# bt_bio.net
KiCad netlist of a schematic drawn in EAGLE
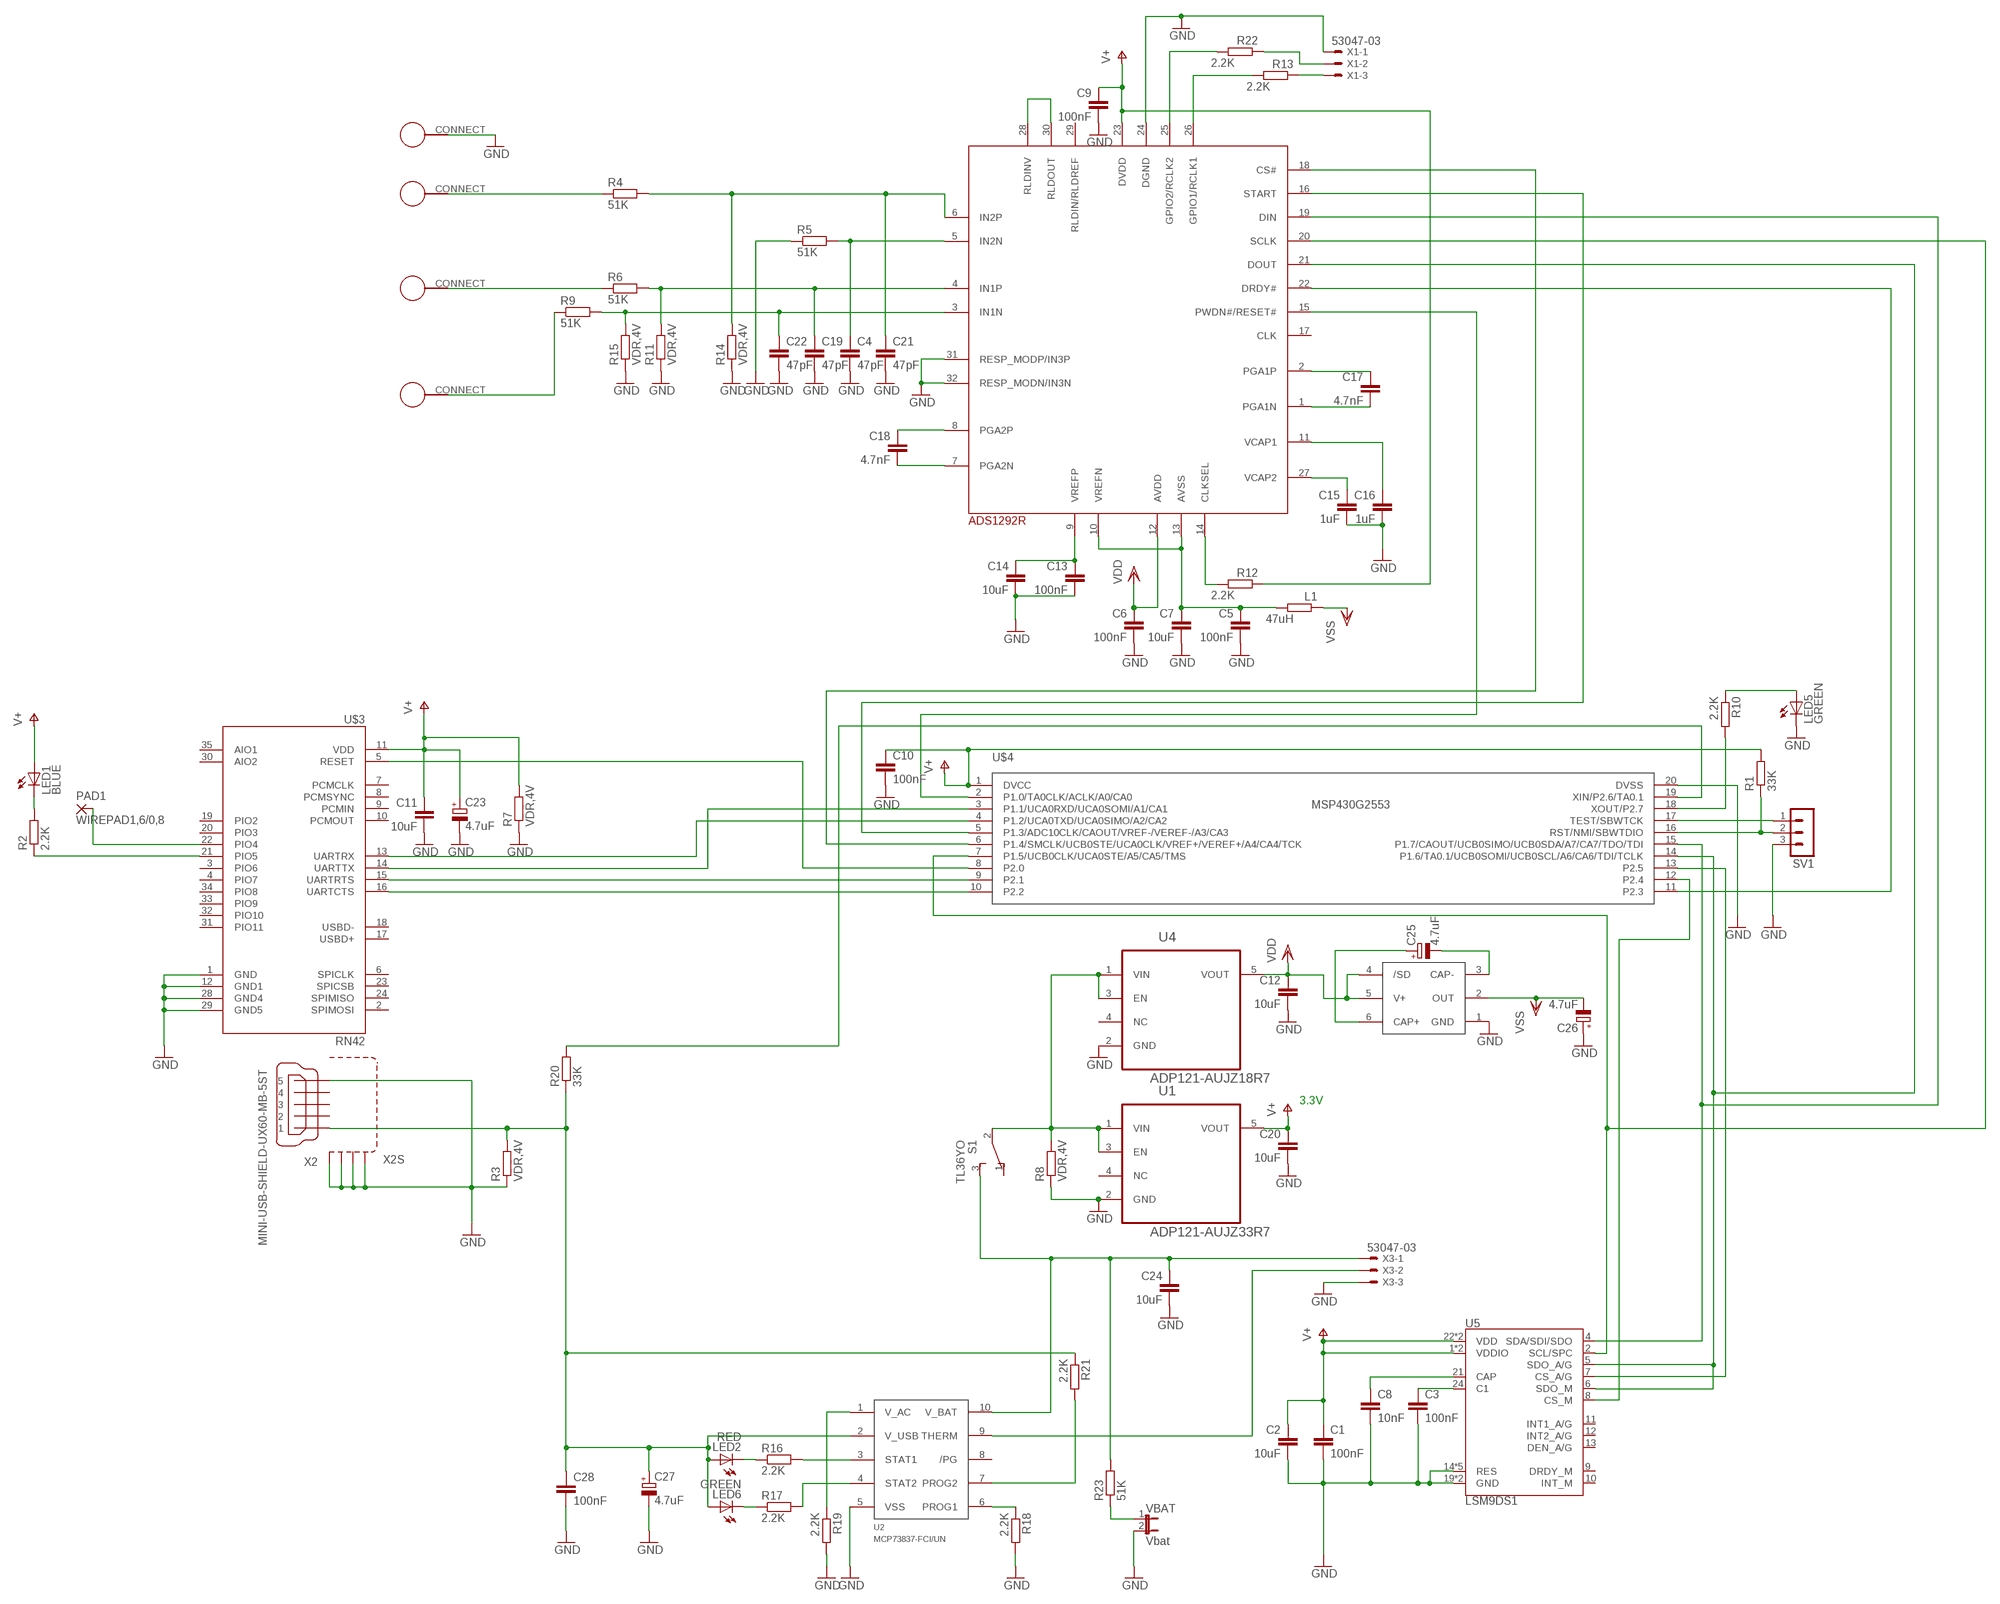
[diagram p0: schematic, sheet 1]

(export (version "E")
  (design (tool "Eeschema 10.0.6"))
  (components
    (comp (ref "ADS1292R")
      (value "ADS1292R")
      (footprint "eagle-import:TQFP-32")
      (libsource (lib "eagle-import") (part "ADS1292R"))
    )
    (comp (ref "C1")
      (value "100nF")
      (footprint "eagle-import:C0603")
      (libsource (lib "eagle-import") (part "C-EUC0603"))
    )
    (comp (ref "C2")
      (value "10uF")
      (footprint "eagle-import:C1206")
      (libsource (lib "eagle-import") (part "C-EUC1206"))
    )
    (comp (ref "C3")
      (value "100nF")
      (footprint "eagle-import:C0603")
      (libsource (lib "eagle-import") (part "C-EUC0603"))
    )
    (comp (ref "C4")
      (value "47pF")
      (footprint "eagle-import:C0603")
      (libsource (lib "eagle-import") (part "C-EUC0603"))
    )
    (comp (ref "C5")
      (value "100nF")
      (footprint "eagle-import:C0603")
      (libsource (lib "eagle-import") (part "C-EUC0603"))
    )
    (comp (ref "C6")
      (value "100nF")
      (footprint "eagle-import:C0603")
      (libsource (lib "eagle-import") (part "C-EUC0603"))
    )
    (comp (ref "C7")
      (value "10uF")
      (footprint "eagle-import:C1206")
      (libsource (lib "eagle-import") (part "C-EUC1206"))
    )
    (comp (ref "C8")
      (value "10nF")
      (footprint "eagle-import:C0603")
      (libsource (lib "eagle-import") (part "C-EUC0603"))
    )
    (comp (ref "C9")
      (value "100nF")
      (footprint "eagle-import:C0603")
      (libsource (lib "eagle-import") (part "C-EUC0603"))
    )
    (comp (ref "C10")
      (value "100nF")
      (footprint "eagle-import:C0603")
      (libsource (lib "eagle-import") (part "C-EUC0603"))
    )
    (comp (ref "C11")
      (value "10uF")
      (footprint "eagle-import:C1206")
      (libsource (lib "eagle-import") (part "C-EUC1206"))
    )
    (comp (ref "C12")
      (value "10uF")
      (footprint "eagle-import:C1206")
      (libsource (lib "eagle-import") (part "C-EUC1206"))
    )
    (comp (ref "C13")
      (value "100nF")
      (footprint "eagle-import:C0603")
      (libsource (lib "eagle-import") (part "C-EUC0603"))
    )
    (comp (ref "C14")
      (value "10uF")
      (footprint "eagle-import:C1206")
      (libsource (lib "eagle-import") (part "C-EUC1206"))
    )
    (comp (ref "C15")
      (value "1uF")
      (footprint "eagle-import:C0603")
      (libsource (lib "eagle-import") (part "C-EUC0603"))
    )
    (comp (ref "C16")
      (value "1uF")
      (footprint "eagle-import:C0603")
      (libsource (lib "eagle-import") (part "C-EUC0603"))
    )
    (comp (ref "C17")
      (value "4.7nF")
      (footprint "eagle-import:C0603")
      (libsource (lib "eagle-import") (part "C-EUC0603"))
    )
    (comp (ref "C18")
      (value "4.7nF")
      (footprint "eagle-import:C0603")
      (libsource (lib "eagle-import") (part "C-EUC0603"))
    )
    (comp (ref "C19")
      (value "47pF")
      (footprint "eagle-import:C0603")
      (libsource (lib "eagle-import") (part "C-EUC0603"))
    )
    (comp (ref "C20")
      (value "10uF")
      (footprint "eagle-import:C1206")
      (libsource (lib "eagle-import") (part "C-EUC1206"))
    )
    (comp (ref "C21")
      (value "47pF")
      (footprint "eagle-import:C0603")
      (libsource (lib "eagle-import") (part "C-EUC0603"))
    )
    (comp (ref "C22")
      (value "47pF")
      (footprint "eagle-import:C0603")
      (libsource (lib "eagle-import") (part "C-EUC0603"))
    )
    (comp (ref "C23")
      (value "4.7uF")
      (footprint "eagle-import:SMC_C")
      (libsource (lib "eagle-import") (part "CPOL-EUSMCC"))
    )
    (comp (ref "C24")
      (value "10uF")
      (footprint "eagle-import:C1206")
      (libsource (lib "eagle-import") (part "C-EUC1206"))
    )
    (comp (ref "C25")
      (value "4.7uF")
      (footprint "eagle-import:SMC_C")
      (libsource (lib "eagle-import") (part "CPOL-EUSMCC"))
    )
    (comp (ref "C26")
      (value "4.7uF")
      (footprint "eagle-import:SMC_C")
      (libsource (lib "eagle-import") (part "CPOL-EUSMCC"))
    )
    (comp (ref "C27")
      (value "4.7uF")
      (footprint "eagle-import:SMC_C")
      (libsource (lib "eagle-import") (part "CPOL-EUSMCC"))
    )
    (comp (ref "C28")
      (value "100nF")
      (footprint "eagle-import:C0603")
      (libsource (lib "eagle-import") (part "C-EUC0603"))
    )
    (comp (ref "L1")
      (value "47uH")
      (footprint "eagle-import:R0805")
      (libsource (lib "eagle-import") (part "R-EU_R0805"))
    )
    (comp (ref "LED1")
      (value "BLUE")
      (footprint "eagle-import:CHIPLED_0805")
      (libsource (lib "eagle-import") (part "LEDCHIPLED_0805"))
    )
    (comp (ref "LED2")
      (value "RED")
      (footprint "eagle-import:CHIPLED_0805")
      (libsource (lib "eagle-import") (part "LEDCHIPLED_0805"))
    )
    (comp (ref "LED5")
      (value "GREEN")
      (footprint "eagle-import:CHIPLED_0805")
      (libsource (lib "eagle-import") (part "LEDCHIPLED_0805"))
    )
    (comp (ref "LED6")
      (value "GREEN")
      (footprint "eagle-import:CHIPLED_0805")
      (libsource (lib "eagle-import") (part "LEDCHIPLED_0805"))
    )
    (comp (ref "PAD1")
      (value "WIREPAD1,6/0,8")
      (footprint "eagle-import:1,6_0,8")
      (libsource (lib "eagle-import") (part "WIREPAD1,6/0,8"))
    )
    (comp (ref "R1")
      (value "33K")
      (footprint "eagle-import:R0603")
      (libsource (lib "eagle-import") (part "resistor_R-EU_R0603"))
    )
    (comp (ref "R2")
      (value "2.2K")
      (footprint "eagle-import:R0603")
      (libsource (lib "eagle-import") (part "R-EU_R0603"))
    )
    (comp (ref "R3")
      (value "VDR,4V")
      (footprint "eagle-import:R0805")
      (libsource (lib "eagle-import") (part "R-EU_R0805"))
    )
    (comp (ref "R4")
      (value "51K")
      (footprint "eagle-import:R0603")
      (libsource (lib "eagle-import") (part "R-EU_R0603"))
    )
    (comp (ref "R5")
      (value "51K")
      (footprint "eagle-import:R0603")
      (libsource (lib "eagle-import") (part "R-EU_R0603"))
    )
    (comp (ref "R6")
      (value "51K")
      (footprint "eagle-import:R0603")
      (libsource (lib "eagle-import") (part "R-EU_R0603"))
    )
    (comp (ref "R7")
      (value "VDR,4V")
      (footprint "eagle-import:R0805")
      (libsource (lib "eagle-import") (part "R-EU_R0805"))
    )
    (comp (ref "R8")
      (value "VDR,4V")
      (footprint "eagle-import:R0805")
      (libsource (lib "eagle-import") (part "R-EU_R0805"))
    )
    (comp (ref "R9")
      (value "51K")
      (footprint "eagle-import:R0603")
      (libsource (lib "eagle-import") (part "R-EU_R0603"))
    )
    (comp (ref "R10")
      (value "2.2K")
      (footprint "eagle-import:R0603")
      (libsource (lib "eagle-import") (part "R-EU_R0603"))
    )
    (comp (ref "R11")
      (value "VDR,4V")
      (footprint "eagle-import:R0805")
      (libsource (lib "eagle-import") (part "R-EU_R0805"))
    )
    (comp (ref "R12")
      (value "2.2K")
      (footprint "eagle-import:R0603")
      (libsource (lib "eagle-import") (part "R-EU_R0603"))
    )
    (comp (ref "R13")
      (value "2.2K")
      (footprint "eagle-import:R0603")
      (libsource (lib "eagle-import") (part "R-EU_R0603"))
    )
    (comp (ref "R14")
      (value "VDR,4V")
      (footprint "eagle-import:R0805")
      (libsource (lib "eagle-import") (part "R-EU_R0805"))
    )
    (comp (ref "R15")
      (value "VDR,4V")
      (footprint "eagle-import:R0805")
      (libsource (lib "eagle-import") (part "R-EU_R0805"))
    )
    (comp (ref "R16")
      (value "2.2K")
      (footprint "eagle-import:R0603")
      (libsource (lib "eagle-import") (part "R-EU_R0603"))
    )
    (comp (ref "R17")
      (value "2.2K")
      (footprint "eagle-import:R0603")
      (libsource (lib "eagle-import") (part "R-EU_R0603"))
    )
    (comp (ref "R18")
      (value "2.2K")
      (footprint "eagle-import:R0603")
      (libsource (lib "eagle-import") (part "R-EU_R0603"))
    )
    (comp (ref "R19")
      (value "2.2K")
      (footprint "eagle-import:R0603")
      (libsource (lib "eagle-import") (part "R-EU_R0603"))
    )
    (comp (ref "R20")
      (value "33K")
      (footprint "eagle-import:R0603")
      (libsource (lib "eagle-import") (part "resistor_R-EU_R0603"))
    )
    (comp (ref "R21")
      (value "2.2K")
      (footprint "eagle-import:R0603")
      (libsource (lib "eagle-import") (part "R-EU_R0603"))
    )
    (comp (ref "R22")
      (value "2.2K")
      (footprint "eagle-import:R0603")
      (libsource (lib "eagle-import") (part "R-EU_R0603"))
    )
    (comp (ref "R23")
      (value "51K")
      (footprint "eagle-import:R0603")
      (libsource (lib "eagle-import") (part "R-EU_R0603"))
    )
    (comp (ref "S1")
      (value "TL36YO")
      (footprint "eagle-import:TL3XYO")
      (libsource (lib "eagle-import") (part "TL36YO"))
    )
    (comp (ref "SV1")
      (value "MA03-1")
      (footprint "eagle-import:MA03-1")
      (libsource (lib "eagle-import") (part "MA03-1"))
    )
    (comp (ref "U$3")
      (value "RN42")
      (footprint "eagle-import:SPARKFUN_RN41")
      (libsource (lib "eagle-import") (part "SPARKFUN_BLUETOOTH-RN41{dblquote}"))
    )
    (comp (ref "U$4")
      (value "MSP430G2553")
      (footprint "eagle-import:TSSOP20")
      (libsource (lib "eagle-import") (part "MSP430G2553"))
    )
    (comp (ref "U$5")
      (value "4MMCONNECT")
      (footprint "eagle-import:4MMCONNECT")
      (libsource (lib "eagle-import") (part "4MMCONNECT"))
    )
    (comp (ref "U$7")
      (value "4MMCONNECT")
      (footprint "eagle-import:4MMCONNECT")
      (libsource (lib "eagle-import") (part "4MMCONNECT"))
    )
    (comp (ref "U$9")
      (value "4MMCONNECT")
      (footprint "eagle-import:4MMCONNECT")
      (libsource (lib "eagle-import") (part "4MMCONNECT"))
    )
    (comp (ref "U$10")
      (value "4MMCONNECT")
      (footprint "eagle-import:4MMCONNECT")
      (libsource (lib "eagle-import") (part "4MMCONNECT"))
    )
    (comp (ref "U$12")
      (value "LM2664")
      (footprint "eagle-import:SOT-23-5")
      (libsource (lib "eagle-import") (part "LM2664"))
    )
    (comp (ref "U1")
      (value "ADP121-AUJZ33R7")
      (footprint "eagle-import:SOT95P280X100-5N")
      (libsource (lib "eagle-import") (part "ADP121-AUJZ33R7"))
    )
    (comp (ref "U2")
      (value "MCP73837-FCI/UN")
      (footprint "eagle-import:MSOP10")
      (libsource (lib "eagle-import") (part "MCP73837"))
    )
    (comp (ref "U4")
      (value "ADP121-AUJZ18R7")
      (footprint "eagle-import:SOT95P280X100-5N")
      (fields (field (name "MPN") "ADP121-AUJZ33R7"))
      (libsource (lib "eagle-import") (part "ADP121-AUJZ33R7"))
    )
    (comp (ref "U5")
      (value "LSM9DS1")
      (footprint "eagle-import:LGA24-8X4")
      (libsource (lib "eagle-import") (part "LSM9DS1"))
    )
    (comp (ref "VBAT")
      (value "Vbat")
      (footprint "eagle-import:JP1")
      (libsource (lib "eagle-import") (part "JP1E"))
    )
    (comp (ref "X1")
      (value "53047-03")
      (footprint "eagle-import:53047-03")
      (fields (field (name "MPN") "530470310"))
      (libsource (lib "eagle-import") (part "53?-03047"))
    )
    (comp (ref "X2")
      (value "MINI-USB-SHIELD-UX60-MB-5ST")
      (footprint "eagle-import:UX60-MB-5ST")
      (libsource (lib "eagle-import") (part "MINI-USB-SHIELD-UX60-MB-5ST"))
    )
    (comp (ref "X3")
      (value "53047-03")
      (footprint "eagle-import:53047-03")
      (fields (field (name "MPN") "530470310"))
      (libsource (lib "eagle-import") (part "53?-03047"))
    )
  )
  (nets
    (net (code "1") (name "GND") (class "Default")
      (node (ref "ADS1292R") (pin "24") (pinfunction "DGND_24") (pintype "bidirectional"))
      (node (ref "ADS1292R") (pin "31") (pinfunction "RESP_MODP/IN3P_31") (pintype "bidirectional"))
      (node (ref "ADS1292R") (pin "32") (pinfunction "RESP_MODN/IN3N_32") (pintype "bidirectional"))
      (node (ref "C1") (pin "2") (pinfunction "2_2") (pintype "passive"))
      (node (ref "C10") (pin "2") (pinfunction "2_2") (pintype "passive"))
      (node (ref "C11") (pin "2") (pinfunction "2_2") (pintype "passive"))
      (node (ref "C12") (pin "2") (pinfunction "2_2") (pintype "passive"))
      (node (ref "C13") (pin "2") (pinfunction "2_2") (pintype "passive"))
      (node (ref "C14") (pin "2") (pinfunction "2_2") (pintype "passive"))
      (node (ref "C15") (pin "2") (pinfunction "2_2") (pintype "passive"))
      (node (ref "C16") (pin "2") (pinfunction "2_2") (pintype "passive"))
      (node (ref "C19") (pin "2") (pinfunction "2_2") (pintype "passive"))
      (node (ref "C2") (pin "2") (pinfunction "2_2") (pintype "passive"))
      (node (ref "C20") (pin "2") (pinfunction "2_2") (pintype "passive"))
      (node (ref "C21") (pin "2") (pinfunction "2_2") (pintype "passive"))
      (node (ref "C22") (pin "2") (pinfunction "2_2") (pintype "passive"))
      (node (ref "C23") (pin "-") (pinfunction "-_-") (pintype "passive"))
      (node (ref "C24") (pin "2") (pinfunction "2_2") (pintype "passive"))
      (node (ref "C26") (pin "+") (pinfunction "+_+") (pintype "passive"))
      (node (ref "C27") (pin "-") (pinfunction "-_-") (pintype "passive"))
      (node (ref "C28") (pin "2") (pinfunction "2_2") (pintype "passive"))
      (node (ref "C3") (pin "2") (pinfunction "2_2") (pintype "passive"))
      (node (ref "C4") (pin "2") (pinfunction "2_2") (pintype "passive"))
      (node (ref "C5") (pin "2") (pinfunction "2_2") (pintype "passive"))
      (node (ref "C6") (pin "2") (pinfunction "2_2") (pintype "passive"))
      (node (ref "C7") (pin "2") (pinfunction "2_2") (pintype "passive"))
      (node (ref "C8") (pin "2") (pinfunction "2_2") (pintype "passive"))
      (node (ref "C9") (pin "2") (pinfunction "2_2") (pintype "passive"))
      (node (ref "LED5") (pin "C") (pinfunction "C_C") (pintype "passive"))
      (node (ref "R11") (pin "1") (pinfunction "1_1") (pintype "passive"))
      (node (ref "R14") (pin "1") (pinfunction "1_1") (pintype "passive"))
      (node (ref "R15") (pin "1") (pinfunction "1_1") (pintype "passive"))
      (node (ref "R18") (pin "2") (pinfunction "2_2") (pintype "passive"))
      (node (ref "R19") (pin "2") (pinfunction "2_2") (pintype "passive"))
      (node (ref "R3") (pin "1") (pinfunction "1_1") (pintype "passive"))
      (node (ref "R5") (pin "1") (pinfunction "1_1") (pintype "passive"))
      (node (ref "R7") (pin "1") (pinfunction "1_1") (pintype "passive"))
      (node (ref "R8") (pin "1") (pinfunction "1_1") (pintype "passive"))
      (node (ref "SV1") (pin "3") (pinfunction "3_3") (pintype "passive"))
      (node (ref "U$12") (pin "1") (pinfunction "GND_1") (pintype "power_in"))
      (node (ref "U$3") (pin "1") (pinfunction "GND_1") (pintype "bidirectional"))
      (node (ref "U$3") (pin "12") (pinfunction "GND1_12") (pintype "bidirectional"))
      (node (ref "U$3") (pin "28") (pinfunction "GND4_28") (pintype "bidirectional"))
      (node (ref "U$3") (pin "29") (pinfunction "GND5_29") (pintype "bidirectional"))
      (node (ref "U$4") (pin "20") (pinfunction "DVSS_20") (pintype "bidirectional"))
      (node (ref "U$5") (pin "CONNECT") (pinfunction "CONNECT_CONNECT") (pintype "passive"))
      (node (ref "U1") (pin "2") (pinfunction "GND_2") (pintype "passive"))
      (node (ref "U2") (pin "5") (pinfunction "VSS_5") (pintype "bidirectional"))
      (node (ref "U4") (pin "2") (pinfunction "GND_2") (pintype "passive"))
      (node (ref "U5") (pin "14") (pinfunction "RES_14") (pintype "bidirectional"))
      (node (ref "U5") (pin "15") (pinfunction "RES_15") (pintype "bidirectional"))
      (node (ref "U5") (pin "16") (pinfunction "RES_16") (pintype "bidirectional"))
      (node (ref "U5") (pin "17") (pinfunction "RES_17") (pintype "bidirectional"))
      (node (ref "U5") (pin "18") (pinfunction "RES_18") (pintype "bidirectional"))
      (node (ref "U5") (pin "19") (pinfunction "GND_19") (pintype "bidirectional"))
      (node (ref "U5") (pin "20") (pinfunction "GND_20") (pintype "bidirectional"))
      (node (ref "VBAT") (pin "2") (pinfunction "2_2") (pintype "passive"))
      (node (ref "X1") (pin "1") (pinfunction "S_1") (pintype "passive"))
      (node (ref "X2") (pin "5") (pinfunction "5_5") (pintype "input"))
      (node (ref "X2") (pin "M1") (pinfunction "S1_M1") (pintype "passive"))
      (node (ref "X2") (pin "M2") (pinfunction "S2_M2") (pintype "passive"))
      (node (ref "X2") (pin "M3") (pinfunction "S3_M3") (pintype "passive"))
      (node (ref "X2") (pin "M4") (pinfunction "S4_M4") (pintype "passive"))
      (node (ref "X3") (pin "3") (pinfunction "S_3") (pintype "passive"))
    )
    (net (code "2") (name "Net-(ADS1292R-AVSS)") (class "Default")
      (node (ref "ADS1292R") (pin "10") (pinfunction "VREFN_10") (pintype "bidirectional"))
      (node (ref "ADS1292R") (pin "13") (pinfunction "AVSS_13") (pintype "bidirectional"))
      (node (ref "C5") (pin "1") (pinfunction "1_1") (pintype "passive"))
      (node (ref "C7") (pin "1") (pinfunction "1_1") (pintype "passive"))
      (node (ref "L1") (pin "2") (pinfunction "2_2") (pintype "passive"))
    )
    (net (code "3") (name "Net-(ADS1292R-CLKSEL)") (class "Default")
      (node (ref "ADS1292R") (pin "14") (pinfunction "CLKSEL_14") (pintype "bidirectional"))
      (node (ref "R12") (pin "2") (pinfunction "2_2") (pintype "passive"))
    )
    (net (code "4") (name "Net-(ADS1292R-CS#)") (class "Default")
      (node (ref "ADS1292R") (pin "18") (pinfunction "CS#_18") (pintype "bidirectional"))
      (node (ref "U$4") (pin "6") (pinfunction "P1.4/SMCLK/UCB0STE/UCA0CLK/VREF+/VEREF+/A4/CA4/TCK_6") (pintype "bidirectional"))
    )
    (net (code "5") (name "Net-(ADS1292R-DIN)") (class "Default")
      (node (ref "ADS1292R") (pin "19") (pinfunction "DIN_19") (pintype "bidirectional"))
      (node (ref "U$4") (pin "15") (pinfunction "P1.7/CAOUT/UCB0SIMO/UCB0SDA/A7/CA7/TDO/TDI_15") (pintype "bidirectional"))
      (node (ref "U5") (pin "4") (pinfunction "SDA/SDI/SDO_4") (pintype "bidirectional"))
    )
    (net (code "6") (name "Net-(ADS1292R-DOUT)") (class "Default")
      (node (ref "ADS1292R") (pin "21") (pinfunction "DOUT_21") (pintype "bidirectional"))
      (node (ref "U$4") (pin "14") (pinfunction "P1.6/TA0.1/UCB0SOMI/UCB0SCL/A6/CA6/TDI/TCLK_14") (pintype "bidirectional"))
      (node (ref "U5") (pin "5") (pinfunction "SDO_A/G_5") (pintype "bidirectional"))
      (node (ref "U5") (pin "6") (pinfunction "SDO_M_6") (pintype "bidirectional"))
    )
    (net (code "7") (name "Net-(ADS1292R-DRDY#)") (class "Default")
      (node (ref "ADS1292R") (pin "22") (pinfunction "DRDY#_22") (pintype "bidirectional"))
      (node (ref "U$4") (pin "11") (pinfunction "P2.3_11") (pintype "bidirectional"))
    )
    (net (code "8") (name "Net-(ADS1292R-GPIO1{slash}RCLK1)") (class "Default")
      (node (ref "ADS1292R") (pin "26") (pinfunction "GPIO1/RCLK1_26") (pintype "bidirectional"))
      (node (ref "R13") (pin "2") (pinfunction "2_2") (pintype "passive"))
    )
    (net (code "9") (name "Net-(ADS1292R-GPIO2{slash}RCLK2)") (class "Default")
      (node (ref "ADS1292R") (pin "25") (pinfunction "GPIO2/RCLK2_25") (pintype "bidirectional"))
      (node (ref "R22") (pin "2") (pinfunction "2_2") (pintype "passive"))
    )
    (net (code "10") (name "Net-(ADS1292R-IN1N)") (class "Default")
      (node (ref "ADS1292R") (pin "3") (pinfunction "IN1N_3") (pintype "bidirectional"))
      (node (ref "C22") (pin "1") (pinfunction "1_1") (pintype "passive"))
      (node (ref "R15") (pin "2") (pinfunction "2_2") (pintype "passive"))
      (node (ref "R9") (pin "2") (pinfunction "2_2") (pintype "passive"))
    )
    (net (code "11") (name "Net-(ADS1292R-IN1P)") (class "Default")
      (node (ref "ADS1292R") (pin "4") (pinfunction "IN1P_4") (pintype "bidirectional"))
      (node (ref "C19") (pin "1") (pinfunction "1_1") (pintype "passive"))
      (node (ref "R11") (pin "2") (pinfunction "2_2") (pintype "passive"))
      (node (ref "R6") (pin "2") (pinfunction "2_2") (pintype "passive"))
    )
    (net (code "12") (name "Net-(ADS1292R-IN2N)") (class "Default")
      (node (ref "ADS1292R") (pin "5") (pinfunction "IN2N_5") (pintype "bidirectional"))
      (node (ref "C4") (pin "1") (pinfunction "1_1") (pintype "passive"))
      (node (ref "R5") (pin "2") (pinfunction "2_2") (pintype "passive"))
    )
    (net (code "13") (name "Net-(ADS1292R-IN2P)") (class "Default")
      (node (ref "ADS1292R") (pin "6") (pinfunction "IN2P_6") (pintype "bidirectional"))
      (node (ref "C21") (pin "1") (pinfunction "1_1") (pintype "passive"))
      (node (ref "R14") (pin "2") (pinfunction "2_2") (pintype "passive"))
      (node (ref "R4") (pin "2") (pinfunction "2_2") (pintype "passive"))
    )
    (net (code "14") (name "Net-(ADS1292R-PGA1N)") (class "Default")
      (node (ref "ADS1292R") (pin "1") (pinfunction "PGA1N_1") (pintype "bidirectional"))
      (node (ref "C17") (pin "2") (pinfunction "2_2") (pintype "passive"))
    )
    (net (code "15") (name "Net-(ADS1292R-PGA1P)") (class "Default")
      (node (ref "ADS1292R") (pin "2") (pinfunction "PGA1P_2") (pintype "bidirectional"))
      (node (ref "C17") (pin "1") (pinfunction "1_1") (pintype "passive"))
    )
    (net (code "16") (name "Net-(ADS1292R-PGA2N)") (class "Default")
      (node (ref "ADS1292R") (pin "7") (pinfunction "PGA2N_7") (pintype "bidirectional"))
      (node (ref "C18") (pin "2") (pinfunction "2_2") (pintype "passive"))
    )
    (net (code "17") (name "Net-(ADS1292R-PGA2P)") (class "Default")
      (node (ref "ADS1292R") (pin "8") (pinfunction "PGA2P_8") (pintype "bidirectional"))
      (node (ref "C18") (pin "1") (pinfunction "1_1") (pintype "passive"))
    )
    (net (code "18") (name "Net-(ADS1292R-PWDN#{slash}RESET#)") (class "Default")
      (node (ref "ADS1292R") (pin "15") (pinfunction "PWDN#/RESET#_15") (pintype "bidirectional"))
      (node (ref "U$4") (pin "2") (pinfunction "P1.0/TA0CLK/ACLK/A0/CA0_2") (pintype "bidirectional"))
    )
    (net (code "19") (name "Net-(ADS1292R-RLDINV)") (class "Default")
      (node (ref "ADS1292R") (pin "28") (pinfunction "RLDINV_28") (pintype "bidirectional"))
      (node (ref "ADS1292R") (pin "30") (pinfunction "RLDOUT_30") (pintype "bidirectional"))
    )
    (net (code "20") (name "Net-(ADS1292R-SCLK)") (class "Default")
      (node (ref "ADS1292R") (pin "20") (pinfunction "SCLK_20") (pintype "bidirectional"))
      (node (ref "U$4") (pin "7") (pinfunction "P1.5/UCB0CLK/UCA0STE/A5/CA5/TMS_7") (pintype "bidirectional"))
      (node (ref "U5") (pin "2") (pinfunction "SCL/SPC_2") (pintype "bidirectional"))
    )
    (net (code "21") (name "Net-(ADS1292R-START)") (class "Default")
      (node (ref "ADS1292R") (pin "16") (pinfunction "START_16") (pintype "bidirectional"))
      (node (ref "U$4") (pin "5") (pinfunction "P1.3/ADC10CLK/CAOUT/VREF-/VEREF-/A3/CA3_5") (pintype "bidirectional"))
    )
    (net (code "22") (name "Net-(ADS1292R-VCAP1)") (class "Default")
      (node (ref "ADS1292R") (pin "11") (pinfunction "VCAP1_11") (pintype "bidirectional"))
      (node (ref "C16") (pin "1") (pinfunction "1_1") (pintype "passive"))
    )
    (net (code "23") (name "Net-(ADS1292R-VCAP2)") (class "Default")
      (node (ref "ADS1292R") (pin "27") (pinfunction "VCAP2_27") (pintype "bidirectional"))
      (node (ref "C15") (pin "1") (pinfunction "1_1") (pintype "passive"))
    )
    (net (code "24") (name "Net-(ADS1292R-VREFP)") (class "Default")
      (node (ref "ADS1292R") (pin "9") (pinfunction "VREFP_9") (pintype "bidirectional"))
      (node (ref "C13") (pin "1") (pinfunction "1_1") (pintype "passive"))
      (node (ref "C14") (pin "1") (pinfunction "1_1") (pintype "passive"))
    )
    (net (code "25") (name "Net-(LED1-PadC)") (class "Default")
      (node (ref "LED1") (pin "C") (pinfunction "C_C") (pintype "passive"))
      (node (ref "R2") (pin "2") (pinfunction "2_2") (pintype "passive"))
    )
    (net (code "26") (name "Net-(LED2-PadC)") (class "Default")
      (node (ref "LED2") (pin "C") (pinfunction "C_C") (pintype "passive"))
      (node (ref "R16") (pin "1") (pinfunction "1_1") (pintype "passive"))
    )
    (net (code "27") (name "Net-(LED5-PadA)") (class "Default")
      (node (ref "LED5") (pin "A") (pinfunction "A_A") (pintype "passive"))
      (node (ref "R10") (pin "1") (pinfunction "1_1") (pintype "passive"))
    )
    (net (code "28") (name "Net-(LED6-PadC)") (class "Default")
      (node (ref "LED6") (pin "C") (pinfunction "C_C") (pintype "passive"))
      (node (ref "R17") (pin "1") (pinfunction "1_1") (pintype "passive"))
    )
    (net (code "29") (name "Net-(PAD1-P)") (class "Default")
      (node (ref "PAD1") (pin "1") (pinfunction "P_1") (pintype "passive"))
      (node (ref "U$3") (pin "22") (pinfunction "PIO4_22") (pintype "bidirectional"))
    )
    (net (code "30") (name "Net-(R4-Pad1)") (class "Default")
      (node (ref "R4") (pin "1") (pinfunction "1_1") (pintype "passive"))
      (node (ref "U$7") (pin "CONNECT") (pinfunction "CONNECT_CONNECT") (pintype "passive"))
    )
    (net (code "31") (name "Net-(R6-Pad1)") (class "Default")
      (node (ref "R6") (pin "1") (pinfunction "1_1") (pintype "passive"))
      (node (ref "U$9") (pin "CONNECT") (pinfunction "CONNECT_CONNECT") (pintype "passive"))
    )
    (net (code "32") (name "Net-(R9-Pad1)") (class "Default")
      (node (ref "R9") (pin "1") (pinfunction "1_1") (pintype "passive"))
      (node (ref "U$10") (pin "CONNECT") (pinfunction "CONNECT_CONNECT") (pintype "passive"))
    )
    (net (code "33") (name "Net-(R23-Pad1)") (class "Default")
      (node (ref "R23") (pin "1") (pinfunction "1_1") (pintype "passive"))
      (node (ref "VBAT") (pin "1") (pinfunction "1_1") (pintype "passive"))
    )
    (net (code "34") (name "Net-(S1-P)") (class "Default")
      (node (ref "R8") (pin "2") (pinfunction "2_2") (pintype "passive"))
      (node (ref "S1") (pin "2") (pinfunction "P_2") (pintype "passive"))
      (node (ref "U1") (pin "1") (pinfunction "VIN_1") (pintype "input"))
      (node (ref "U1") (pin "3") (pinfunction "EN_3") (pintype "input"))
      (node (ref "U4") (pin "1") (pinfunction "VIN_1") (pintype "input"))
      (node (ref "U4") (pin "3") (pinfunction "EN_3") (pintype "input"))
    )
    (net (code "35") (name "Net-(S1-S)") (class "Default")
      (node (ref "C24") (pin "1") (pinfunction "1_1") (pintype "passive"))
      (node (ref "R23") (pin "2") (pinfunction "2_2") (pintype "passive"))
      (node (ref "S1") (pin "3") (pinfunction "S_3") (pintype "passive"))
      (node (ref "U2") (pin "10") (pinfunction "V_BAT_10") (pintype "bidirectional"))
      (node (ref "X3") (pin "1") (pinfunction "S_1") (pintype "passive"))
    )
    (net (code "36") (name "Net-(U$3-PIO5)") (class "Default")
      (node (ref "R2") (pin "1") (pinfunction "1_1") (pintype "passive"))
      (node (ref "U$3") (pin "21") (pinfunction "PIO5_21") (pintype "bidirectional"))
    )
    (net (code "37") (name "Net-(U$3-RESET)") (class "Default")
      (node (ref "U$3") (pin "5") (pinfunction "RESET_5") (pintype "bidirectional"))
      (node (ref "U$4") (pin "8") (pinfunction "P2.0_8") (pintype "bidirectional"))
    )
    (net (code "38") (name "Net-(U$3-UARTCTS)") (class "Default")
      (node (ref "U$3") (pin "16") (pinfunction "UARTCTS_16") (pintype "bidirectional"))
      (node (ref "U$4") (pin "10") (pinfunction "P2.2_10") (pintype "bidirectional"))
    )
    (net (code "39") (name "Net-(U$3-UARTRTS)") (class "Default")
      (node (ref "U$3") (pin "15") (pinfunction "UARTRTS_15") (pintype "bidirectional"))
      (node (ref "U$4") (pin "9") (pinfunction "P2.1_9") (pintype "bidirectional"))
    )
    (net (code "40") (name "Net-(U$3-UARTRX)") (class "Default")
      (node (ref "U$3") (pin "13") (pinfunction "UARTRX_13") (pintype "bidirectional"))
      (node (ref "U$4") (pin "4") (pinfunction "P1.2/UCA0TXD/UCA0SIMO/A2/CA2_4") (pintype "bidirectional"))
    )
    (net (code "41") (name "Net-(U$3-UARTTX)") (class "Default")
      (node (ref "U$3") (pin "14") (pinfunction "UARTTX_14") (pintype "bidirectional"))
      (node (ref "U$4") (pin "3") (pinfunction "P1.1/UCA0RXD/UCA0SOMI/A1/CA1_3") (pintype "bidirectional"))
    )
    (net (code "42") (name "Net-(U$4-P2.4)") (class "Default")
      (node (ref "U$4") (pin "12") (pinfunction "P2.4_12") (pintype "bidirectional"))
      (node (ref "U5") (pin "8") (pinfunction "CS_M_8") (pintype "bidirectional"))
    )
    (net (code "43") (name "Net-(U$4-P2.5)") (class "Default")
      (node (ref "U$4") (pin "13") (pinfunction "P2.5_13") (pintype "bidirectional"))
      (node (ref "U5") (pin "7") (pinfunction "CS_A/G_7") (pintype "bidirectional"))
    )
    (net (code "44") (name "Net-(U$4-RST{slash}NMI{slash}SBWTDIO)") (class "Default")
      (node (ref "R1") (pin "1") (pinfunction "1_1") (pintype "passive"))
      (node (ref "SV1") (pin "2") (pinfunction "2_2") (pintype "passive"))
      (node (ref "U$4") (pin "16") (pinfunction "RST/NMI/SBWTDIO_16") (pintype "bidirectional"))
    )
    (net (code "45") (name "Net-(U$4-TEST{slash}SBWTCK)") (class "Default")
      (node (ref "SV1") (pin "1") (pinfunction "1_1") (pintype "passive"))
      (node (ref "U$4") (pin "17") (pinfunction "TEST/SBWTCK_17") (pintype "bidirectional"))
    )
    (net (code "46") (name "Net-(U$4-XIN{slash}P2.6{slash}TA0.1)") (class "Default")
      (node (ref "R20") (pin "2") (pinfunction "2_2") (pintype "passive"))
      (node (ref "U$4") (pin "19") (pinfunction "XIN/P2.6/TA0.1_19") (pintype "bidirectional"))
    )
    (net (code "47") (name "Net-(U$4-XOUT{slash}P2.7)") (class "Default")
      (node (ref "R10") (pin "2") (pinfunction "2_2") (pintype "passive"))
      (node (ref "U$4") (pin "18") (pinfunction "XOUT/P2.7_18") (pintype "bidirectional"))
    )
    (net (code "48") (name "Net-(U$12-CAP+)") (class "Default")
      (node (ref "C25") (pin "+") (pinfunction "+_+") (pintype "passive"))
      (node (ref "U$12") (pin "6") (pinfunction "CAP+_6") (pintype "bidirectional"))
    )
    (net (code "49") (name "Net-(U$12-CAP-)") (class "Default")
      (node (ref "C25") (pin "-") (pinfunction "-_-") (pintype "passive"))
      (node (ref "U$12") (pin "3") (pinfunction "CAP-_3") (pintype "bidirectional"))
    )
    (net (code "50") (name "Net-(U2-PROG1)") (class "Default")
      (node (ref "R18") (pin "1") (pinfunction "1_1") (pintype "passive"))
      (node (ref "U2") (pin "6") (pinfunction "PROG1_6") (pintype "bidirectional"))
    )
    (net (code "51") (name "Net-(U2-PROG2)") (class "Default")
      (node (ref "R21") (pin "2") (pinfunction "2_2") (pintype "passive"))
      (node (ref "U2") (pin "7") (pinfunction "PROG2_7") (pintype "bidirectional"))
    )
    (net (code "52") (name "Net-(U2-STAT1)") (class "Default")
      (node (ref "R16") (pin "2") (pinfunction "2_2") (pintype "passive"))
      (node (ref "U2") (pin "3") (pinfunction "STAT1_3") (pintype "bidirectional"))
    )
    (net (code "53") (name "Net-(U2-STAT2)") (class "Default")
      (node (ref "R17") (pin "2") (pinfunction "2_2") (pintype "passive"))
      (node (ref "U2") (pin "4") (pinfunction "STAT2_4") (pintype "bidirectional"))
    )
    (net (code "54") (name "Net-(U2-THERM)") (class "Default")
      (node (ref "U2") (pin "9") (pinfunction "THERM_9") (pintype "bidirectional"))
      (node (ref "X3") (pin "2") (pinfunction "S_2") (pintype "passive"))
    )
    (net (code "55") (name "Net-(U2-V_AC)") (class "Default")
      (node (ref "R19") (pin "1") (pinfunction "1_1") (pintype "passive"))
      (node (ref "U2") (pin "1") (pinfunction "V_AC_1") (pintype "bidirectional"))
    )
    (net (code "56") (name "Net-(U2-V_USB)") (class "Default")
      (node (ref "C27") (pin "+") (pinfunction "+_+") (pintype "passive"))
      (node (ref "C28") (pin "1") (pinfunction "1_1") (pintype "passive"))
      (node (ref "LED2") (pin "A") (pinfunction "A_A") (pintype "passive"))
      (node (ref "LED6") (pin "A") (pinfunction "A_A") (pintype "passive"))
      (node (ref "R20") (pin "1") (pinfunction "1_1") (pintype "passive"))
      (node (ref "R21") (pin "1") (pinfunction "1_1") (pintype "passive"))
      (node (ref "R3") (pin "2") (pinfunction "2_2") (pintype "passive"))
      (node (ref "U2") (pin "2") (pinfunction "V_USB_2") (pintype "bidirectional"))
      (node (ref "X2") (pin "1") (pinfunction "1_1") (pintype "input"))
    )
    (net (code "57") (name "Net-(U5-C1)") (class "Default")
      (node (ref "C3") (pin "1") (pinfunction "1_1") (pintype "passive"))
      (node (ref "U5") (pin "24") (pinfunction "C1_24") (pintype "bidirectional"))
    )
    (net (code "58") (name "Net-(U5-CAP)") (class "Default")
      (node (ref "C8") (pin "1") (pinfunction "1_1") (pintype "passive"))
      (node (ref "U5") (pin "21") (pinfunction "CAP_21") (pintype "bidirectional"))
    )
    (net (code "59") (name "Net-(X1B-S)") (class "Default")
      (node (ref "R22") (pin "1") (pinfunction "1_1") (pintype "passive"))
      (node (ref "X1") (pin "2") (pinfunction "S_2") (pintype "passive"))
    )
    (net (code "60") (name "Net-(X1C-S)") (class "Default")
      (node (ref "R13") (pin "1") (pinfunction "1_1") (pintype "passive"))
      (node (ref "X1") (pin "3") (pinfunction "S_3") (pintype "passive"))
    )
    (net (code "61") (name "V+") (class "Default")
      (node (ref "ADS1292R") (pin "23") (pinfunction "DVDD_23") (pintype "bidirectional"))
      (node (ref "C1") (pin "1") (pinfunction "1_1") (pintype "passive"))
      (node (ref "C10") (pin "1") (pinfunction "1_1") (pintype "passive"))
      (node (ref "C11") (pin "1") (pinfunction "1_1") (pintype "passive"))
      (node (ref "C2") (pin "1") (pinfunction "1_1") (pintype "passive"))
      (node (ref "C20") (pin "1") (pinfunction "1_1") (pintype "passive"))
      (node (ref "C23") (pin "+") (pinfunction "+_+") (pintype "passive"))
      (node (ref "C9") (pin "1") (pinfunction "1_1") (pintype "passive"))
      (node (ref "LED1") (pin "A") (pinfunction "A_A") (pintype "passive"))
      (node (ref "R1") (pin "2") (pinfunction "2_2") (pintype "passive"))
      (node (ref "R12") (pin "1") (pinfunction "1_1") (pintype "passive"))
      (node (ref "R7") (pin "2") (pinfunction "2_2") (pintype "passive"))
      (node (ref "U$3") (pin "11") (pinfunction "VDD_11") (pintype "bidirectional"))
      (node (ref "U$4") (pin "1") (pinfunction "DVCC_1") (pintype "bidirectional"))
      (node (ref "U1") (pin "5") (pinfunction "VOUT_5") (pintype "output"))
      (node (ref "U5") (pin "1") (pinfunction "VDDIO_1") (pintype "bidirectional"))
      (node (ref "U5") (pin "22") (pinfunction "VDD_22") (pintype "bidirectional"))
      (node (ref "U5") (pin "23") (pinfunction "VDD_23") (pintype "bidirectional"))
      (node (ref "U5") (pin "3") (pinfunction "VDDIO_3") (pintype "bidirectional"))
    )
    (net (code "62") (name "VDD") (class "Default")
      (node (ref "ADS1292R") (pin "12") (pinfunction "AVDD_12") (pintype "bidirectional"))
      (node (ref "C12") (pin "1") (pinfunction "1_1") (pintype "passive"))
      (node (ref "C6") (pin "1") (pinfunction "1_1") (pintype "passive"))
      (node (ref "U$12") (pin "4") (pinfunction "/SD_4") (pintype "bidirectional"))
      (node (ref "U$12") (pin "5") (pinfunction "V+_5") (pintype "power_in"))
      (node (ref "U4") (pin "5") (pinfunction "VOUT_5") (pintype "output"))
    )
    (net (code "63") (name "VSS") (class "Default")
      (node (ref "C26") (pin "-") (pinfunction "-_-") (pintype "passive"))
      (node (ref "L1") (pin "1") (pinfunction "1_1") (pintype "passive"))
      (node (ref "U$12") (pin "2") (pinfunction "OUT_2") (pintype "bidirectional"))
    )
    (net (code "64") (name "unconnected-(ADS1292R-CLK-Pad17)") (class "Default")
      (node (ref "ADS1292R") (pin "17") (pinfunction "CLK_17") (pintype "bidirectional"))
    )
    (net (code "65") (name "unconnected-(ADS1292R-RLDIN{slash}RLDREF-Pad29)") (class "Default")
      (node (ref "ADS1292R") (pin "29") (pinfunction "RLDIN/RLDREF_29") (pintype "bidirectional"))
    )
    (net (code "66") (name "unconnected-(S1-O-Pad1)") (class "Default")
      (node (ref "S1") (pin "1") (pinfunction "O_1") (pintype "passive"))
    )
    (net (code "67") (name "unconnected-(U$3-AIO1-Pad35)") (class "Default")
      (node (ref "U$3") (pin "35") (pinfunction "AIO1_35") (pintype "bidirectional"))
    )
    (net (code "68") (name "unconnected-(U$3-AIO2-Pad30)") (class "Default")
      (node (ref "U$3") (pin "30") (pinfunction "AIO2_30") (pintype "bidirectional"))
    )
    (net (code "69") (name "unconnected-(U$3-PCMCLK-Pad7)") (class "Default")
      (node (ref "U$3") (pin "7") (pinfunction "PCMCLK_7") (pintype "bidirectional"))
    )
    (net (code "70") (name "unconnected-(U$3-PCMIN-Pad9)") (class "Default")
      (node (ref "U$3") (pin "9") (pinfunction "PCMIN_9") (pintype "bidirectional"))
    )
    (net (code "71") (name "unconnected-(U$3-PCMOUT-Pad10)") (class "Default")
      (node (ref "U$3") (pin "10") (pinfunction "PCMOUT_10") (pintype "bidirectional"))
    )
    (net (code "72") (name "unconnected-(U$3-PCMSYNC-Pad8)") (class "Default")
      (node (ref "U$3") (pin "8") (pinfunction "PCMSYNC_8") (pintype "bidirectional"))
    )
    (net (code "73") (name "unconnected-(U$3-PIO2-Pad19)") (class "Default")
      (node (ref "U$3") (pin "19") (pinfunction "PIO2_19") (pintype "bidirectional"))
    )
    (net (code "74") (name "unconnected-(U$3-PIO3-Pad20)") (class "Default")
      (node (ref "U$3") (pin "20") (pinfunction "PIO3_20") (pintype "bidirectional"))
    )
    (net (code "75") (name "unconnected-(U$3-PIO6-Pad3)") (class "Default")
      (node (ref "U$3") (pin "3") (pinfunction "PIO6_3") (pintype "bidirectional"))
    )
    (net (code "76") (name "unconnected-(U$3-PIO7-Pad4)") (class "Default")
      (node (ref "U$3") (pin "4") (pinfunction "PIO7_4") (pintype "bidirectional"))
    )
    (net (code "77") (name "unconnected-(U$3-PIO8-Pad34)") (class "Default")
      (node (ref "U$3") (pin "34") (pinfunction "PIO8_34") (pintype "bidirectional"))
    )
    (net (code "78") (name "unconnected-(U$3-PIO9-Pad33)") (class "Default")
      (node (ref "U$3") (pin "33") (pinfunction "PIO9_33") (pintype "bidirectional"))
    )
    (net (code "79") (name "unconnected-(U$3-PIO10-Pad32)") (class "Default")
      (node (ref "U$3") (pin "32") (pinfunction "PIO10_32") (pintype "bidirectional"))
    )
    (net (code "80") (name "unconnected-(U$3-PIO11-Pad31)") (class "Default")
      (node (ref "U$3") (pin "31") (pinfunction "PIO11_31") (pintype "bidirectional"))
    )
    (net (code "81") (name "unconnected-(U$3-SPICLK-Pad6)") (class "Default")
      (node (ref "U$3") (pin "6") (pinfunction "SPICLK_6") (pintype "bidirectional"))
    )
    (net (code "82") (name "unconnected-(U$3-SPICSB-Pad23)") (class "Default")
      (node (ref "U$3") (pin "23") (pinfunction "SPICSB_23") (pintype "bidirectional"))
    )
    (net (code "83") (name "unconnected-(U$3-SPIMISO-Pad24)") (class "Default")
      (node (ref "U$3") (pin "24") (pinfunction "SPIMISO_24") (pintype "bidirectional"))
    )
    (net (code "84") (name "unconnected-(U$3-SPIMOSI-Pad2)") (class "Default")
      (node (ref "U$3") (pin "2") (pinfunction "SPIMOSI_2") (pintype "bidirectional"))
    )
    (net (code "85") (name "unconnected-(U$3-USBD+-Pad17)") (class "Default")
      (node (ref "U$3") (pin "17") (pinfunction "USBD+_17") (pintype "bidirectional"))
    )
    (net (code "86") (name "unconnected-(U$3-USBD--Pad18)") (class "Default")
      (node (ref "U$3") (pin "18") (pinfunction "USBD-_18") (pintype "bidirectional"))
    )
    (net (code "87") (name "unconnected-(U1-NC-Pad4)") (class "Default")
      (node (ref "U1") (pin "4") (pinfunction "NC_4") (pintype "no_connect"))
    )
    (net (code "88") (name "unconnected-(U2-{slash}PG-Pad8)") (class "Default")
      (node (ref "U2") (pin "8") (pinfunction "/PG_8") (pintype "bidirectional"))
    )
    (net (code "89") (name "unconnected-(U4-NC-Pad4)") (class "Default")
      (node (ref "U4") (pin "4") (pinfunction "NC_4") (pintype "no_connect"))
    )
    (net (code "90") (name "unconnected-(U5-DEN_A{slash}G-Pad13)") (class "Default")
      (node (ref "U5") (pin "13") (pinfunction "DEN_A/G_13") (pintype "bidirectional"))
    )
    (net (code "91") (name "unconnected-(U5-DRDY_M-Pad9)") (class "Default")
      (node (ref "U5") (pin "9") (pinfunction "DRDY_M_9") (pintype "bidirectional"))
    )
    (net (code "92") (name "unconnected-(U5-INT1_A{slash}G-Pad11)") (class "Default")
      (node (ref "U5") (pin "11") (pinfunction "INT1_A/G_11") (pintype "bidirectional"))
    )
    (net (code "93") (name "unconnected-(U5-INT2_A{slash}G-Pad12)") (class "Default")
      (node (ref "U5") (pin "12") (pinfunction "INT2_A/G_12") (pintype "bidirectional"))
    )
    (net (code "94") (name "unconnected-(U5-INT_M-Pad10)") (class "Default")
      (node (ref "U5") (pin "10") (pinfunction "INT_M_10") (pintype "bidirectional"))
    )
    (net (code "95") (name "unconnected-(X2-Pad2)") (class "Default")
      (node (ref "X2") (pin "2") (pinfunction "2_2") (pintype "input"))
    )
    (net (code "96") (name "unconnected-(X2-Pad3)") (class "Default")
      (node (ref "X2") (pin "3") (pinfunction "3_3") (pintype "input"))
    )
    (net (code "97") (name "unconnected-(X2-Pad4)") (class "Default")
      (node (ref "X2") (pin "4") (pinfunction "4_4") (pintype "input"))
    )
  )
)
